# DSO_Control.net
KiCad netlist of a schematic drawn in Altium Designer
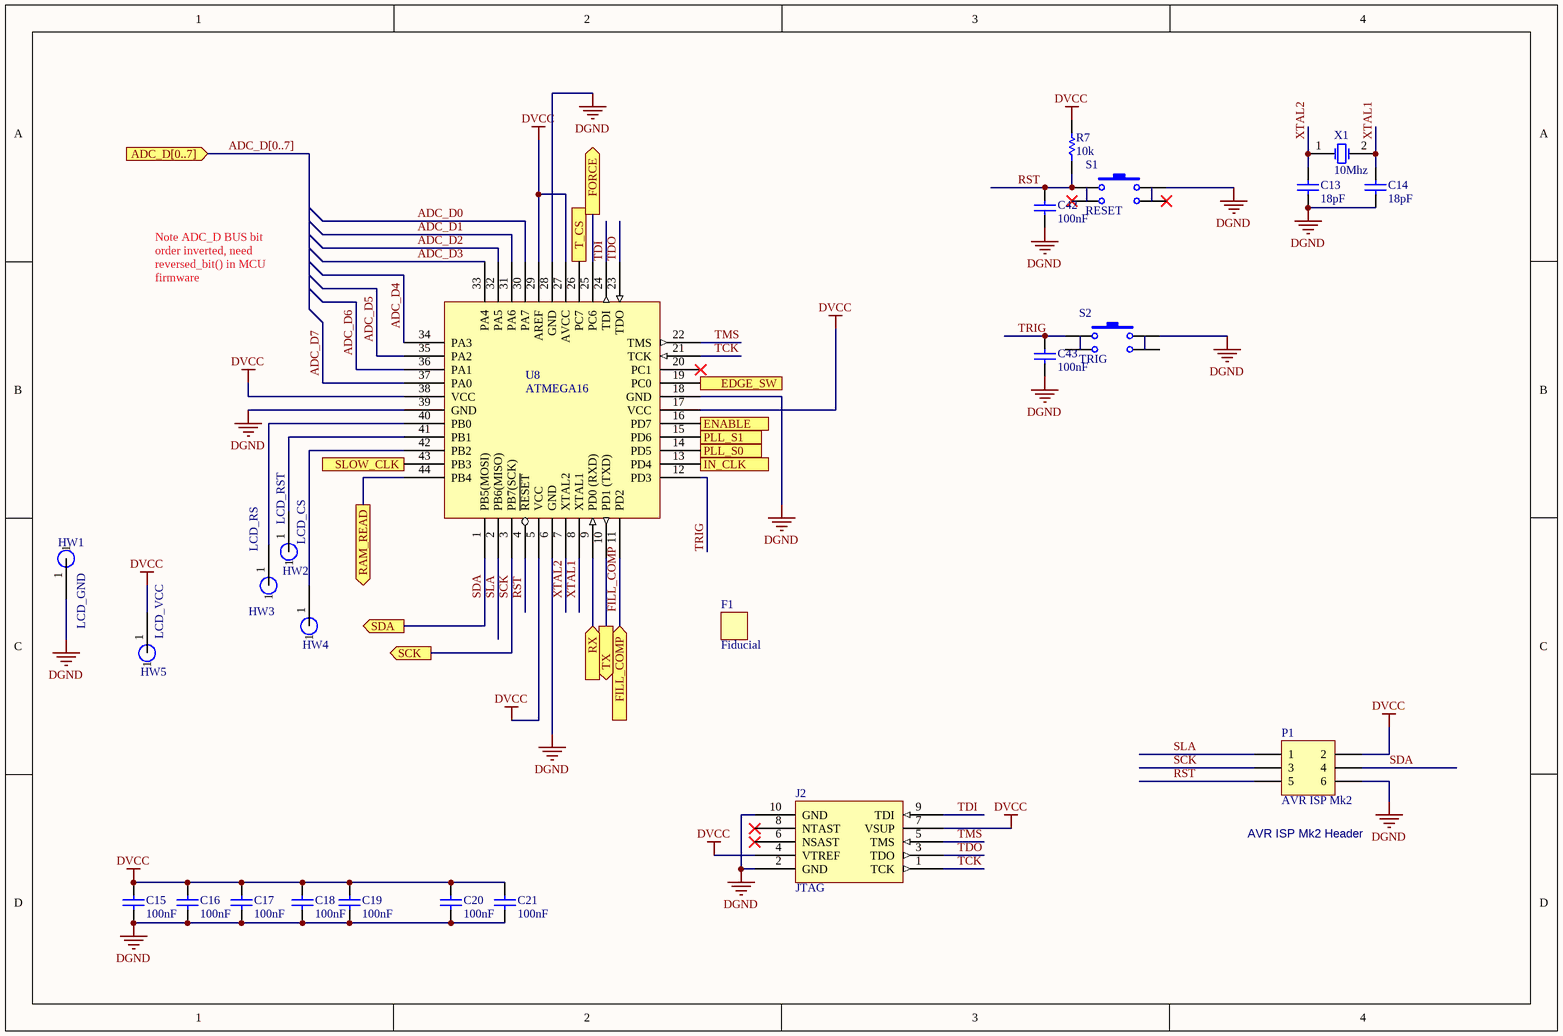
[diagram p0: DSO_Control.SchDoc]

(export (version "E")
  (design (tool "Eeschema 10.0.6"))
  (components
    (comp (ref "C13")
      (value "18pF")
      (footprint "0805C")
      (description "Capacitor")
      (fields (field (name "REVIEWED BY") "RM - 2018/08/05"))
      (libsource (lib "DSO") (part "C"))
    )
    (comp (ref "C14")
      (value "18pF")
      (footprint "0805C")
      (description "Capacitor")
      (fields (field (name "REVIEWED BY") "RM - 2018/08/05"))
      (libsource (lib "DSO") (part "C"))
    )
    (comp (ref "C15")
      (value "100nF")
      (footprint "0805C")
      (description "Capacitor")
      (fields (field (name "REVIEWED BY") "RM - 2018/08/05"))
      (libsource (lib "DSO") (part "C"))
    )
    (comp (ref "C16")
      (value "100nF")
      (footprint "0805C")
      (description "Capacitor")
      (fields (field (name "REVIEWED BY") "RM - 2018/08/05"))
      (libsource (lib "DSO") (part "C"))
    )
    (comp (ref "C17")
      (value "100nF")
      (footprint "0805C")
      (description "Capacitor")
      (fields (field (name "REVIEWED BY") "RM - 2018/08/05"))
      (libsource (lib "DSO") (part "C"))
    )
    (comp (ref "C18")
      (value "100nF")
      (footprint "0805C")
      (description "Capacitor")
      (fields (field (name "REVIEWED BY") "RM - 2018/08/05"))
      (libsource (lib "DSO") (part "C"))
    )
    (comp (ref "C19")
      (value "100nF")
      (footprint "0805C")
      (description "Capacitor")
      (fields (field (name "REVIEWED BY") "RM - 2018/08/05"))
      (libsource (lib "DSO") (part "C"))
    )
    (comp (ref "C20")
      (value "100nF")
      (footprint "0805C")
      (description "Capacitor")
      (fields (field (name "REVIEWED BY") "RM - 2018/08/05"))
      (libsource (lib "DSO") (part "C"))
    )
    (comp (ref "C21")
      (value "100nF")
      (footprint "0805C")
      (description "Capacitor")
      (fields (field (name "REVIEWED BY") "RM - 2018/08/05"))
      (libsource (lib "DSO") (part "C"))
    )
    (comp (ref "C42")
      (value "100nF")
      (footprint "0805C")
      (description "Capacitor")
      (fields (field (name "REVIEWED BY") "RM - 2018/08/05"))
      (libsource (lib "DSO") (part "C"))
    )
    (comp (ref "C43")
      (value "100nF")
      (footprint "0805C")
      (description "Capacitor")
      (fields (field (name "REVIEWED BY") "RM - 2018/08/05"))
      (libsource (lib "DSO") (part "C"))
    )
    (comp (ref "F1") (value "Fiducial") (footprint "Fiducial") (libsource (lib "DSO") (part "Fiducial")))
    (comp (ref "HW1")
      (value "LCD_GND")
      (footprint "HOLE_FOR_WIRE")
      (description "Hole for wire")
      (libsource (lib "DSO") (part "HOLE_FOR_WIRE"))
    )
    (comp (ref "HW2")
      (value "LCD_RST")
      (footprint "HOLE_FOR_WIRE")
      (description "Hole for wire")
      (libsource (lib "DSO") (part "HOLE_FOR_WIRE"))
    )
    (comp (ref "HW3")
      (value "LCD_RS")
      (footprint "HOLE_FOR_WIRE")
      (description "Hole for wire")
      (libsource (lib "DSO") (part "HOLE_FOR_WIRE"))
    )
    (comp (ref "HW4")
      (value "LCD_CS")
      (footprint "HOLE_FOR_WIRE")
      (description "Hole for wire")
      (libsource (lib "DSO") (part "HOLE_FOR_WIRE"))
    )
    (comp (ref "HW5")
      (value "LCD_VCC")
      (footprint "HOLE_FOR_WIRE")
      (description "Hole for wire")
      (libsource (lib "DSO") (part "HOLE_FOR_WIRE"))
    )
    (comp (ref "J2")
      (value "JTAG")
      (footprint "BOXEDVERT10")
      (description "JTAG_CON")
      (fields (field (name "REVIEWED BY") "RM - 2018/08/05"))
      (libsource (lib "DSO") (part "JTAG_CON"))
    )
    (comp (ref "P1")
      (value "AVR ISP Mk2")
      (footprint "HDR3x2")
      (description "Header, 5-Pin")
      (fields (field (name "REVIEWED BY") "RM - 2018/08/05"))
      (libsource (lib "DSO") (part "Header 3x2"))
    )
    (comp (ref "R7")
      (value "10k")
      (footprint "0805")
      (description "Resistor")
      (fields (field (name "REVIEWED BY") "RM - 2018/08/05"))
      (libsource (lib "DSO") (part "R"))
    )
    (comp (ref "S1")
      (value "RESET")
      (footprint "SPST PB SWITCH SMD")
      (description "Momentary Push Button Switch 1P 1T 2pins")
      (fields (field (name "REVIEWED BY") "RM - 2018/08/05"))
      (libsource (lib "DSO") (part "SW_PB_1P1T4"))
    )
    (comp (ref "S2")
      (value "TRIG")
      (footprint "SPST PB SWITCH SMD")
      (description "Momentary Push Button Switch 1P 1T 2pins")
      (fields (field (name "REVIEWED BY") "RM - 2018/08/05"))
      (libsource (lib "DSO") (part "SW_PB_1P1T4"))
    )
    (comp (ref "U8")
      (value "ATMEGA16")
      (footprint "QFP-48")
      (description "ATMEGA16 Microcontroller")
      (fields (field (name "REVIEWED BY") "RM - 2018/08/05"))
      (libsource (lib "DSO") (part "ATMEGA16"))
    )
    (comp (ref "X1")
      (value "10Mhz")
      (footprint "XTAL_FLAT_SMD")
      (description "Crystal Oscillator")
      (fields (field (name "REVIEWED BY") "RM - 2018/08/05"))
      (libsource (lib "DSO") (part "XTAL"))
    )
  )
  (nets
    (net (code "1") (name "/ADC_D0") (class "Default")
      (node (ref "U8") (pin "30") (pinfunction "PA7_30") (pintype "passive"))
    )
    (net (code "2") (name "/ADC_D1") (class "Default")
      (node (ref "U8") (pin "31") (pinfunction "PA6_31") (pintype "passive"))
    )
    (net (code "3") (name "/ADC_D2") (class "Default")
      (node (ref "U8") (pin "32") (pinfunction "PA5_32") (pintype "passive"))
    )
    (net (code "4") (name "/ADC_D3") (class "Default")
      (node (ref "U8") (pin "33") (pinfunction "PA4_33") (pintype "passive"))
    )
    (net (code "5") (name "/ADC_D4") (class "Default")
      (node (ref "U8") (pin "34") (pinfunction "PA3_34") (pintype "passive"))
    )
    (net (code "6") (name "/ADC_D5") (class "Default")
      (node (ref "U8") (pin "35") (pinfunction "PA2_35") (pintype "passive"))
    )
    (net (code "7") (name "/ADC_D6") (class "Default")
      (node (ref "U8") (pin "36") (pinfunction "PA1_36") (pintype "passive"))
    )
    (net (code "8") (name "/ADC_D7") (class "Default")
      (node (ref "U8") (pin "37") (pinfunction "PA0_37") (pintype "passive"))
    )
    (net (code "10") (name "/EDGE_SW") (class "Default")
      (node (ref "U8") (pin "19") (pinfunction "PC0_19") (pintype "passive"))
    )
    (net (code "11") (name "/ENABLE") (class "Default")
      (node (ref "U8") (pin "16") (pinfunction "PD7_16") (pintype "passive"))
    )
    (net (code "12") (name "/FILL_COMP") (class "Default")
      (node (ref "U8") (pin "11") (pinfunction "PD2_11") (pintype "passive"))
    )
    (net (code "13") (name "/FORCE") (class "Default")
      (node (ref "U8") (pin "25") (pinfunction "PC6_25") (pintype "passive"))
    )
    (net (code "14") (name "/IN_CLK") (class "Default")
      (node (ref "U8") (pin "13") (pinfunction "PD4_13") (pintype "passive"))
    )
    (net (code "15") (name "/PLL_S0") (class "Default")
      (node (ref "U8") (pin "14") (pinfunction "PD5_14") (pintype "passive"))
    )
    (net (code "16") (name "/PLL_S1") (class "Default")
      (node (ref "U8") (pin "15") (pinfunction "PD6_15") (pintype "passive"))
    )
    (net (code "17") (name "/RAM_READ") (class "Default")
      (node (ref "U8") (pin "44") (pinfunction "PB4_44") (pintype "passive"))
    )
    (net (code "18") (name "/RST") (class "Default")
      (node (ref "C42") (pin "1") (pinfunction "1_1") (pintype "passive"))
      (node (ref "P1") (pin "5") (pinfunction "5_5") (pintype "passive"))
      (node (ref "R7") (pin "1") (pintype "passive"))
      (node (ref "S1") (pin "1") (pinfunction "1_1") (pintype "passive"))
      (node (ref "U8") (pin "4") (pinfunction "~{RESET}_4") (pintype "passive"))
    )
    (net (code "19") (name "/RX") (class "Default")
      (node (ref "U8") (pin "9") (pinfunction "PD0_(RXD)_9") (pintype "input"))
    )
    (net (code "20") (name "/SCK") (class "Default")
      (node (ref "P1") (pin "3") (pinfunction "3_3") (pintype "passive"))
      (node (ref "U8") (pin "3") (pinfunction "PB7(SCK)_3") (pintype "passive"))
    )
    (net (code "21") (name "/SDA") (class "Default")
      (node (ref "P1") (pin "4") (pinfunction "4_4") (pintype "passive"))
      (node (ref "U8") (pin "1") (pinfunction "PB5(MOSI)_1") (pintype "passive"))
    )
    (net (code "22") (name "/SLA") (class "Default")
      (node (ref "P1") (pin "1") (pinfunction "1_1") (pintype "passive"))
      (node (ref "U8") (pin "2") (pinfunction "PB6(MISO)_2") (pintype "passive"))
    )
    (net (code "23") (name "/SLOW_CLK") (class "Default")
      (node (ref "U8") (pin "43") (pinfunction "PB3_43") (pintype "passive"))
    )
    (net (code "24") (name "/TCK") (class "Default")
      (node (ref "J2") (pin "1") (pinfunction "TCK_1") (pintype "output"))
      (node (ref "U8") (pin "21") (pinfunction "TCK_21") (pintype "input"))
    )
    (net (code "25") (name "/TDI") (class "Default")
      (node (ref "J2") (pin "9") (pinfunction "TDI_9") (pintype "input"))
      (node (ref "U8") (pin "24") (pinfunction "TDI_24") (pintype "output"))
    )
    (net (code "26") (name "/TDO") (class "Default")
      (node (ref "J2") (pin "3") (pinfunction "TDO_3") (pintype "output"))
      (node (ref "U8") (pin "23") (pinfunction "TDO_23") (pintype "input"))
    )
    (net (code "27") (name "/TMS") (class "Default")
      (node (ref "J2") (pin "5") (pinfunction "TMS_5") (pintype "input"))
      (node (ref "U8") (pin "22") (pinfunction "TMS_22") (pintype "output"))
    )
    (net (code "28") (name "/TRIG") (class "Default")
      (node (ref "C43") (pin "1") (pinfunction "1_1") (pintype "passive"))
      (node (ref "S2") (pin "1") (pinfunction "1_1") (pintype "passive"))
      (node (ref "U8") (pin "12") (pinfunction "PD3_12") (pintype "passive"))
    )
    (net (code "29") (name "/TX") (class "Default")
      (node (ref "U8") (pin "10") (pinfunction "PD1_(TXD)_10") (pintype "output"))
    )
    (net (code "30") (name "/T_CS") (class "Default")
      (node (ref "U8") (pin "26") (pinfunction "PC7_26") (pintype "passive"))
    )
    (net (code "31") (name "/XTAL1") (class "Default")
      (node (ref "C14") (pin "1") (pinfunction "1_1") (pintype "passive"))
      (node (ref "U8") (pin "8") (pinfunction "XTAL1_8") (pintype "passive"))
      (node (ref "X1") (pin "2") (pinfunction "OSC2_2") (pintype "passive"))
    )
    (net (code "32") (name "/XTAL2") (class "Default")
      (node (ref "C13") (pin "1") (pinfunction "1_1") (pintype "passive"))
      (node (ref "U8") (pin "7") (pinfunction "XTAL2_7") (pintype "passive"))
      (node (ref "X1") (pin "1") (pinfunction "OSC1_1") (pintype "passive"))
    )
    (net (code "33") (name "DGND") (class "Default")
      (node (ref "C13") (pin "2") (pinfunction "2_2") (pintype "passive"))
      (node (ref "C14") (pin "2") (pinfunction "2_2") (pintype "passive"))
      (node (ref "C15") (pin "2") (pinfunction "2_2") (pintype "passive"))
      (node (ref "C16") (pin "2") (pinfunction "2_2") (pintype "passive"))
      (node (ref "C17") (pin "2") (pinfunction "2_2") (pintype "passive"))
      (node (ref "C18") (pin "2") (pinfunction "2_2") (pintype "passive"))
      (node (ref "C19") (pin "2") (pinfunction "2_2") (pintype "passive"))
      (node (ref "C20") (pin "2") (pinfunction "2_2") (pintype "passive"))
      (node (ref "C21") (pin "2") (pinfunction "2_2") (pintype "passive"))
      (node (ref "C42") (pin "2") (pinfunction "2_2") (pintype "passive"))
      (node (ref "C43") (pin "2") (pinfunction "2_2") (pintype "passive"))
      (node (ref "HW1") (pin "1") (pinfunction "1_1") (pintype "passive"))
      (node (ref "J2") (pin "10") (pinfunction "GND_10") (pintype "passive"))
      (node (ref "J2") (pin "2") (pinfunction "GND_2") (pintype "passive"))
      (node (ref "P1") (pin "6") (pinfunction "6_6") (pintype "passive"))
      (node (ref "S1") (pin "2") (pinfunction "2_2") (pintype "passive"))
      (node (ref "S2") (pin "2") (pinfunction "2_2") (pintype "passive"))
      (node (ref "U8") (pin "18") (pinfunction "GND_18") (pintype "passive"))
      (node (ref "U8") (pin "28") (pinfunction "GND_28") (pintype "passive"))
      (node (ref "U8") (pin "39") (pinfunction "GND_39") (pintype "passive"))
      (node (ref "U8") (pin "6") (pinfunction "GND_6") (pintype "passive"))
    )
    (net (code "34") (name "DVCC") (class "Default")
      (node (ref "C15") (pin "1") (pinfunction "1_1") (pintype "passive"))
      (node (ref "C16") (pin "1") (pinfunction "1_1") (pintype "passive"))
      (node (ref "C17") (pin "1") (pinfunction "1_1") (pintype "passive"))
      (node (ref "C18") (pin "1") (pinfunction "1_1") (pintype "passive"))
      (node (ref "C19") (pin "1") (pinfunction "1_1") (pintype "passive"))
      (node (ref "C20") (pin "1") (pinfunction "1_1") (pintype "passive"))
      (node (ref "C21") (pin "1") (pinfunction "1_1") (pintype "passive"))
      (node (ref "HW5") (pin "1") (pinfunction "1_1") (pintype "passive"))
      (node (ref "J2") (pin "4") (pinfunction "VTREF_4") (pintype "power_in"))
      (node (ref "J2") (pin "7") (pinfunction "VSUP_7") (pintype "passive"))
      (node (ref "P1") (pin "2") (pinfunction "2_2") (pintype "passive"))
      (node (ref "R7") (pin "2") (pintype "passive"))
      (node (ref "U8") (pin "17") (pinfunction "VCC_17") (pintype "passive"))
      (node (ref "U8") (pin "27") (pinfunction "AVCC_27") (pintype "passive"))
      (node (ref "U8") (pin "29") (pinfunction "AREF_29") (pintype "passive"))
      (node (ref "U8") (pin "38") (pinfunction "VCC_38") (pintype "passive"))
      (node (ref "U8") (pin "5") (pinfunction "VCC_5") (pintype "passive"))
    )
    (net (code "35") (name "Net-(U8-PB0)") (class "Default")
      (node (ref "HW3") (pin "1") (pinfunction "1_1") (pintype "passive"))
      (node (ref "U8") (pin "40") (pinfunction "PB0_40") (pintype "passive"))
    )
    (net (code "36") (name "Net-(U8-PB1)") (class "Default")
      (node (ref "HW2") (pin "1") (pinfunction "1_1") (pintype "passive"))
      (node (ref "U8") (pin "41") (pinfunction "PB1_41") (pintype "passive"))
    )
    (net (code "37") (name "Net-(U8-PB2)") (class "Default")
      (node (ref "HW4") (pin "1") (pinfunction "1_1") (pintype "passive"))
      (node (ref "U8") (pin "42") (pinfunction "PB2_42") (pintype "passive"))
    )
    (net (code "38") (name "unconnected-(J2-NSAST-Pad6)") (class "Default")
      (node (ref "J2") (pin "6") (pinfunction "NSAST_6") (pintype "passive+no_connect"))
    )
    (net (code "39") (name "unconnected-(J2-NTAST-Pad8)") (class "Default")
      (node (ref "J2") (pin "8") (pinfunction "NTAST_8") (pintype "passive+no_connect"))
    )
    (net (code "40") (name "unconnected-(S1-Pad3)") (class "Default")
      (node (ref "S1") (pin "3") (pinfunction "3_3") (pintype "passive+no_connect"))
    )
    (net (code "41") (name "unconnected-(S1-Pad4)") (class "Default")
      (node (ref "S1") (pin "4") (pinfunction "4_4") (pintype "passive+no_connect"))
    )
    (net (code "42") (name "unconnected-(S2-Pad3)") (class "Default")
      (node (ref "S2") (pin "3") (pinfunction "3_3") (pintype "passive"))
    )
    (net (code "43") (name "unconnected-(S2-Pad4)") (class "Default")
      (node (ref "S2") (pin "4") (pinfunction "4_4") (pintype "passive"))
    )
    (net (code "44") (name "unconnected-(U8-PC1-Pad20)") (class "Default")
      (node (ref "U8") (pin "20") (pinfunction "PC1_20") (pintype "passive+no_connect"))
    )
  )
)
